# design.net
KiCad netlist of a schematic drawn in Altium Designer
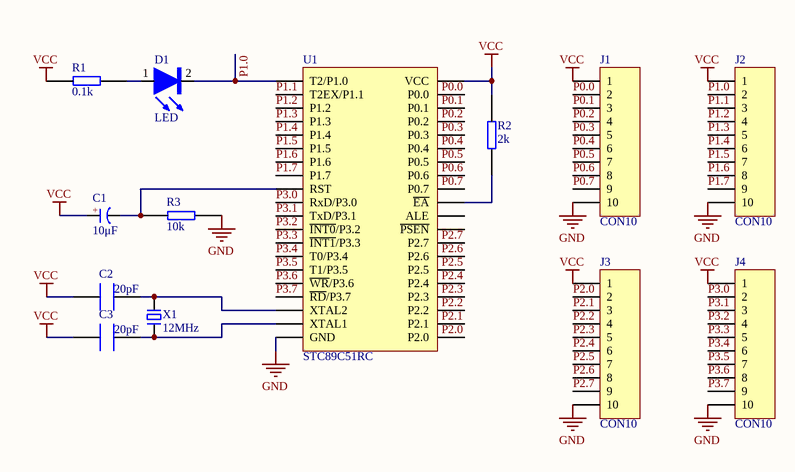
[diagram p0: 核心控制板原理图.SchDoc]

(export (version "E")
  (design (tool "Eeschema 10.0.6"))
  (components
    (comp (ref "C1") (value "10μF") (libsource (lib "Schlib1") (part "极性电容")))
    (comp (ref "C2")
      (value "20pF")
      (footprint "0805C")
      (description "电容")
      (libsource (lib "智能车主板") (part "CAP"))
    )
    (comp (ref "C3")
      (value "20pF")
      (footprint "0805C")
      (description "电容")
      (libsource (lib "智能车主板") (part "CAP"))
    )
    (comp (ref "D1") (value "LED") (footprint "0805D") (libsource (lib "智能车主板") (part "LED")))
    (comp (ref "J1") (value "CON10") (description "Connector") (libsource (lib "智能车主板") (part "CON10")))
    (comp (ref "J2") (value "CON10") (description "Connector") (libsource (lib "智能车主板") (part "CON10")))
    (comp (ref "J3") (value "CON10") (description "Connector") (libsource (lib "智能车主板") (part "CON10")))
    (comp (ref "J4") (value "CON10") (description "Connector") (libsource (lib "智能车主板") (part "CON10")))
    (comp (ref "R1")
      (value "0.1k")
      (footprint "0805R")
      (description "电阻")
      (libsource (lib "智能车主板") (part "RES"))
    )
    (comp (ref "R2")
      (value "2k")
      (footprint "0805R")
      (description "电阻")
      (libsource (lib "智能车主板") (part "RES"))
    )
    (comp (ref "R3")
      (value "10k")
      (footprint "0805R")
      (description "电阻")
      (libsource (lib "智能车主板") (part "RES"))
    )
    (comp (ref "U1")
      (value "STC89C51RC")
      (footprint "DIP40-600")
      (description "STC单片机")
      (fields (field (name "版权归属") "源创客"))
      (libsource (lib "Schlib1") (part "STC89C51RC"))
    )
    (comp (ref "X1")
      (value "12MHz")
      (footprint "OSC HC-49S")
      (description "2脚无源脚晶振")
      (fields (field (name "版权归属") "源创客"))
      (libsource (lib "*") (part "XTAL-2P"))
    )
  )
  (nets
    (net (code "1") (name "/P0.0") (class "Default")
      (node (ref "J1") (pin "2") (pinfunction "2_2") (pintype "passive"))
      (node (ref "U1") (pin "39") (pinfunction "P0.0_39") (pintype "passive"))
    )
    (net (code "2") (name "/P0.1") (class "Default")
      (node (ref "J1") (pin "3") (pinfunction "3_3") (pintype "passive"))
      (node (ref "U1") (pin "38") (pinfunction "P0.1_38") (pintype "passive"))
    )
    (net (code "3") (name "/P0.2") (class "Default")
      (node (ref "J1") (pin "4") (pinfunction "4_4") (pintype "passive"))
      (node (ref "U1") (pin "37") (pinfunction "P0.2_37") (pintype "passive"))
    )
    (net (code "4") (name "/P0.3") (class "Default")
      (node (ref "J1") (pin "5") (pinfunction "5_5") (pintype "passive"))
      (node (ref "U1") (pin "36") (pinfunction "P0.3_36") (pintype "passive"))
    )
    (net (code "5") (name "/P0.4") (class "Default")
      (node (ref "J1") (pin "6") (pinfunction "6_6") (pintype "passive"))
      (node (ref "U1") (pin "35") (pinfunction "P0.4_35") (pintype "passive"))
    )
    (net (code "6") (name "/P0.5") (class "Default")
      (node (ref "J1") (pin "7") (pinfunction "7_7") (pintype "passive"))
      (node (ref "U1") (pin "34") (pinfunction "P0.5_34") (pintype "passive"))
    )
    (net (code "7") (name "/P0.6") (class "Default")
      (node (ref "J1") (pin "8") (pinfunction "8_8") (pintype "passive"))
      (node (ref "U1") (pin "33") (pinfunction "P0.6_33") (pintype "passive"))
    )
    (net (code "8") (name "/P0.7") (class "Default")
      (node (ref "J1") (pin "9") (pinfunction "9_9") (pintype "passive"))
      (node (ref "U1") (pin "32") (pinfunction "P0.7_32") (pintype "passive"))
    )
    (net (code "9") (name "/P1.0") (class "Default")
      (node (ref "D1") (pin "2") (pinfunction "2_2") (pintype "passive"))
      (node (ref "J2") (pin "2") (pinfunction "2_2") (pintype "passive"))
      (node (ref "U1") (pin "1") (pinfunction "T2/P1.0_1") (pintype "passive"))
    )
    (net (code "10") (name "/P1.1") (class "Default")
      (node (ref "J2") (pin "3") (pinfunction "3_3") (pintype "passive"))
      (node (ref "U1") (pin "2") (pinfunction "T2EX/P1.1_2") (pintype "passive"))
    )
    (net (code "11") (name "/P1.2") (class "Default")
      (node (ref "J2") (pin "4") (pinfunction "4_4") (pintype "passive"))
      (node (ref "U1") (pin "3") (pinfunction "P1.2_3") (pintype "passive"))
    )
    (net (code "12") (name "/P1.3") (class "Default")
      (node (ref "J2") (pin "5") (pinfunction "5_5") (pintype "passive"))
      (node (ref "U1") (pin "4") (pinfunction "P1.3_4") (pintype "passive"))
    )
    (net (code "13") (name "/P1.4") (class "Default")
      (node (ref "J2") (pin "6") (pinfunction "6_6") (pintype "passive"))
      (node (ref "U1") (pin "5") (pinfunction "P1.4_5") (pintype "passive"))
    )
    (net (code "14") (name "/P1.5") (class "Default")
      (node (ref "J2") (pin "7") (pinfunction "7_7") (pintype "passive"))
      (node (ref "U1") (pin "6") (pinfunction "P1.5_6") (pintype "passive"))
    )
    (net (code "15") (name "/P1.6") (class "Default")
      (node (ref "J2") (pin "8") (pinfunction "8_8") (pintype "passive"))
      (node (ref "U1") (pin "7") (pinfunction "P1.6_7") (pintype "passive"))
    )
    (net (code "16") (name "/P1.7") (class "Default")
      (node (ref "J2") (pin "9") (pinfunction "9_9") (pintype "passive"))
      (node (ref "U1") (pin "8") (pinfunction "P1.7_8") (pintype "passive"))
    )
    (net (code "17") (name "/P2.0") (class "Default")
      (node (ref "J3") (pin "2") (pinfunction "2_2") (pintype "passive"))
      (node (ref "U1") (pin "21") (pinfunction "P2.0_21") (pintype "passive"))
    )
    (net (code "18") (name "/P2.1") (class "Default")
      (node (ref "J3") (pin "3") (pinfunction "3_3") (pintype "passive"))
      (node (ref "U1") (pin "22") (pinfunction "P2.1_22") (pintype "passive"))
    )
    (net (code "19") (name "/P2.2") (class "Default")
      (node (ref "J3") (pin "4") (pinfunction "4_4") (pintype "passive"))
      (node (ref "U1") (pin "23") (pinfunction "P2.2_23") (pintype "passive"))
    )
    (net (code "20") (name "/P2.3") (class "Default")
      (node (ref "J3") (pin "5") (pinfunction "5_5") (pintype "passive"))
      (node (ref "U1") (pin "24") (pinfunction "P2.3_24") (pintype "passive"))
    )
    (net (code "21") (name "/P2.4") (class "Default")
      (node (ref "J3") (pin "6") (pinfunction "6_6") (pintype "passive"))
      (node (ref "U1") (pin "25") (pinfunction "P2.4_25") (pintype "passive"))
    )
    (net (code "22") (name "/P2.5") (class "Default")
      (node (ref "J3") (pin "7") (pinfunction "7_7") (pintype "passive"))
      (node (ref "U1") (pin "26") (pinfunction "P2.5_26") (pintype "passive"))
    )
    (net (code "23") (name "/P2.6") (class "Default")
      (node (ref "J3") (pin "8") (pinfunction "8_8") (pintype "passive"))
      (node (ref "U1") (pin "27") (pinfunction "P2.6_27") (pintype "passive"))
    )
    (net (code "24") (name "/P2.7") (class "Default")
      (node (ref "J3") (pin "9") (pinfunction "9_9") (pintype "passive"))
      (node (ref "U1") (pin "28") (pinfunction "P2.7_28") (pintype "passive"))
    )
    (net (code "25") (name "/P3.0") (class "Default")
      (node (ref "J4") (pin "2") (pinfunction "2_2") (pintype "passive"))
      (node (ref "U1") (pin "10") (pinfunction "RxD/P3.0_10") (pintype "passive"))
    )
    (net (code "26") (name "/P3.1") (class "Default")
      (node (ref "J4") (pin "3") (pinfunction "3_3") (pintype "passive"))
      (node (ref "U1") (pin "11") (pinfunction "TxD/P3.1_11") (pintype "passive"))
    )
    (net (code "27") (name "/P3.2") (class "Default")
      (node (ref "J4") (pin "4") (pinfunction "4_4") (pintype "passive"))
      (node (ref "U1") (pin "12") (pinfunction "~{INT0}/P3.2_12") (pintype "passive"))
    )
    (net (code "28") (name "/P3.3") (class "Default")
      (node (ref "J4") (pin "5") (pinfunction "5_5") (pintype "passive"))
      (node (ref "U1") (pin "13") (pinfunction "~{INT1}/P3.3_13") (pintype "passive"))
    )
    (net (code "29") (name "/P3.4") (class "Default")
      (node (ref "J4") (pin "6") (pinfunction "6_6") (pintype "passive"))
      (node (ref "U1") (pin "14") (pinfunction "T0/P3.4_14") (pintype "passive"))
    )
    (net (code "30") (name "/P3.5") (class "Default")
      (node (ref "J4") (pin "7") (pinfunction "7_7") (pintype "passive"))
      (node (ref "U1") (pin "15") (pinfunction "T1/P3.5_15") (pintype "passive"))
    )
    (net (code "31") (name "/P3.6") (class "Default")
      (node (ref "J4") (pin "8") (pinfunction "8_8") (pintype "passive"))
      (node (ref "U1") (pin "16") (pinfunction "~{WR}/P3.6_16") (pintype "passive"))
    )
    (net (code "32") (name "/P3.7") (class "Default")
      (node (ref "J4") (pin "9") (pinfunction "9_9") (pintype "passive"))
      (node (ref "U1") (pin "17") (pinfunction "~{RD}/P3.7_17") (pintype "passive"))
    )
    (net (code "33") (name "GND") (class "Default")
      (node (ref "J1") (pin "10") (pinfunction "10_10") (pintype "passive"))
      (node (ref "J2") (pin "10") (pinfunction "10_10") (pintype "passive"))
      (node (ref "J3") (pin "10") (pinfunction "10_10") (pintype "passive"))
      (node (ref "J4") (pin "10") (pinfunction "10_10") (pintype "passive"))
      (node (ref "R3") (pin "1") (pinfunction "1_1") (pintype "passive"))
      (node (ref "U1") (pin "20") (pinfunction "GND_20") (pintype "passive"))
    )
    (net (code "34") (name "Net-(C1-K)") (class "Default")
      (node (ref "C1") (pin "2") (pinfunction "K_2") (pintype "passive"))
      (node (ref "R3") (pin "2") (pinfunction "2_2") (pintype "passive"))
      (node (ref "U1") (pin "9") (pinfunction "RST_9") (pintype "passive"))
    )
    (net (code "35") (name "Net-(D1-Pad1)") (class "Default")
      (node (ref "D1") (pin "1") (pinfunction "1_1") (pintype "passive"))
      (node (ref "R1") (pin "1") (pinfunction "1_1") (pintype "passive"))
    )
    (net (code "36") (name "Net-(U1-XTAL1)") (class "Default")
      (node (ref "C3") (pin "2") (pinfunction "2_2") (pintype "passive"))
      (node (ref "U1") (pin "19") (pinfunction "XTAL1_19") (pintype "passive"))
      (node (ref "X1") (pin "2") (pinfunction "2_2") (pintype "passive"))
    )
    (net (code "37") (name "Net-(U1-XTAL2)") (class "Default")
      (node (ref "C2") (pin "1") (pinfunction "1_1") (pintype "passive"))
      (node (ref "U1") (pin "18") (pinfunction "XTAL2_18") (pintype "passive"))
      (node (ref "X1") (pin "1") (pinfunction "1_1") (pintype "passive"))
    )
    (net (code "38") (name "Net-(U1-~{EA})") (class "Default")
      (node (ref "R2") (pin "1") (pinfunction "1_1") (pintype "passive"))
      (node (ref "U1") (pin "31") (pinfunction "~{EA}_31") (pintype "passive"))
    )
    (net (code "39") (name "VCC") (class "Default")
      (node (ref "C1") (pin "1") (pinfunction "A_1") (pintype "passive"))
      (node (ref "C2") (pin "2") (pinfunction "2_2") (pintype "passive"))
      (node (ref "C3") (pin "1") (pinfunction "1_1") (pintype "passive"))
      (node (ref "J1") (pin "1") (pinfunction "1_1") (pintype "passive"))
      (node (ref "J2") (pin "1") (pinfunction "1_1") (pintype "passive"))
      (node (ref "J3") (pin "1") (pinfunction "1_1") (pintype "passive"))
      (node (ref "J4") (pin "1") (pinfunction "1_1") (pintype "passive"))
      (node (ref "R1") (pin "2") (pinfunction "2_2") (pintype "passive"))
      (node (ref "R2") (pin "2") (pinfunction "2_2") (pintype "passive"))
      (node (ref "U1") (pin "40") (pinfunction "VCC_40") (pintype "passive"))
    )
    (net (code "40") (name "unconnected-(U1-ALE-Pad30)") (class "Default")
      (node (ref "U1") (pin "30") (pinfunction "ALE_30") (pintype "passive"))
    )
    (net (code "41") (name "unconnected-(U1-~{PSEN}-Pad29)") (class "Default")
      (node (ref "U1") (pin "29") (pinfunction "~{PSEN}_29") (pintype "passive"))
    )
  )
)
